# MCUPCB.net
KiCad netlist of a schematic drawn in EasyEDA Pro
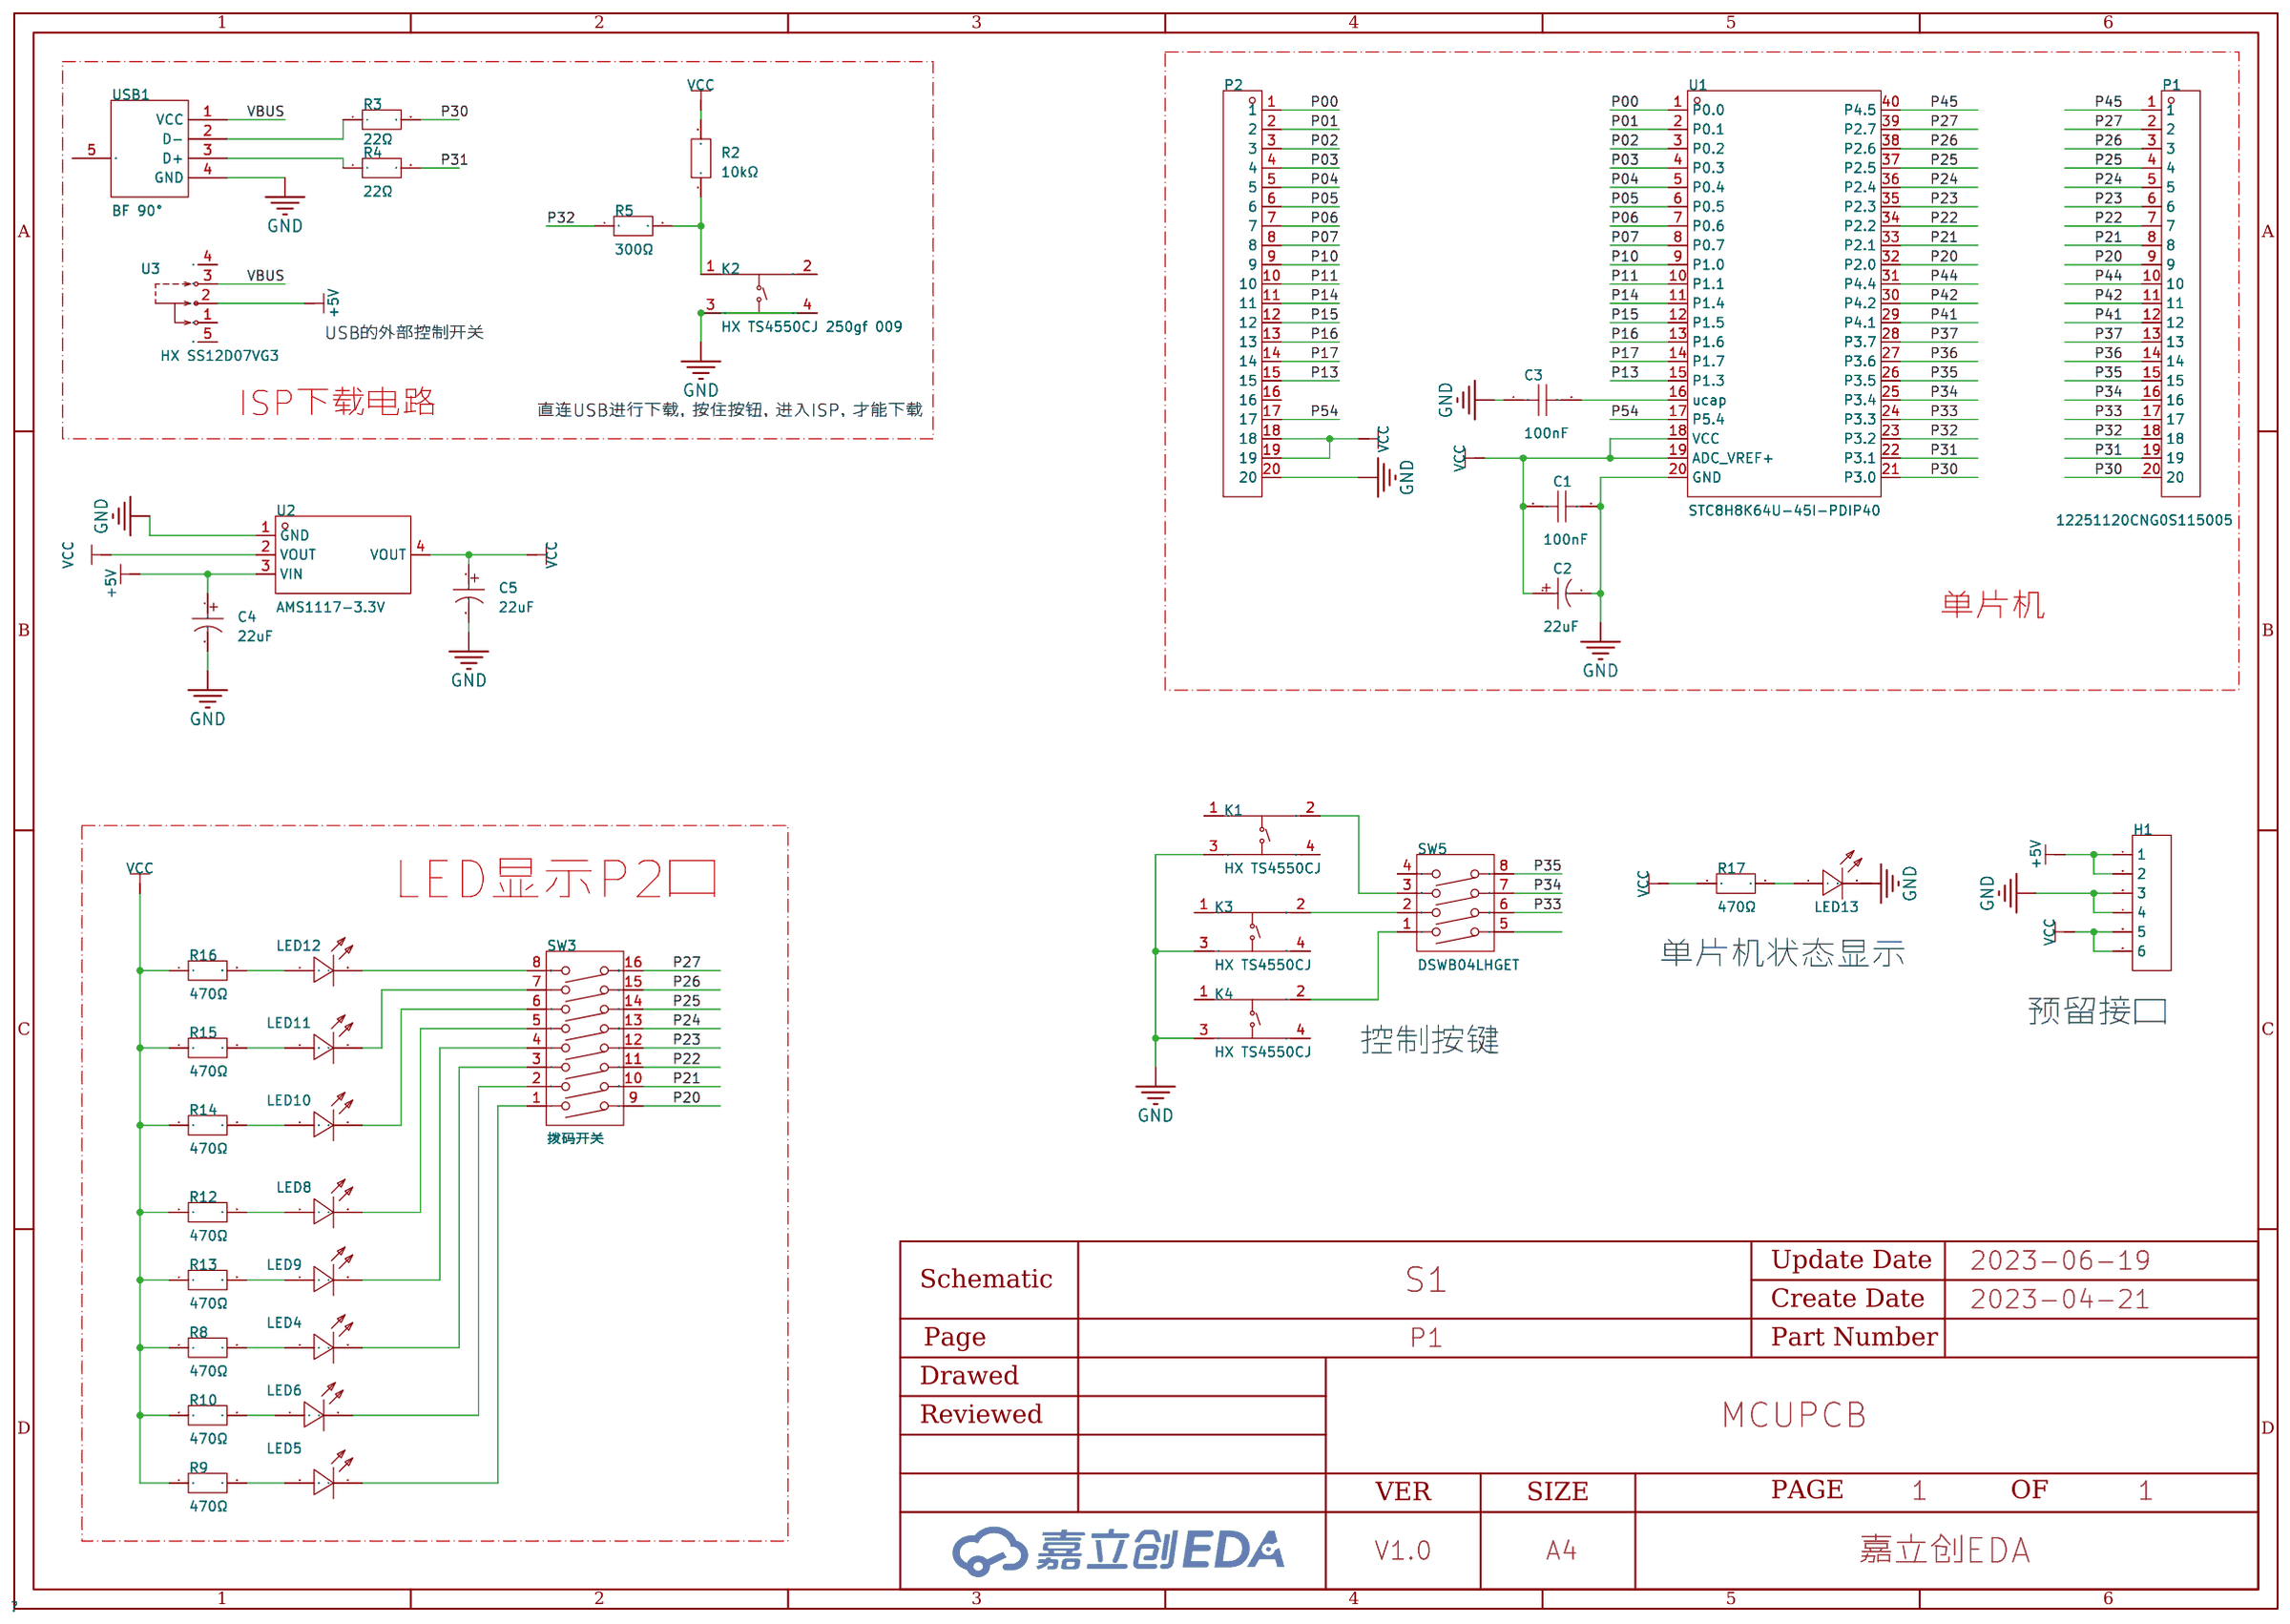
[diagram p0: schematic sheet]

(export (version "E")
  (design (tool "Eeschema 10.0.6"))
  (components
    (comp (ref "C1")
      (value "100nF")
      (footprint "easyedapro:CAP-TH_L4.2-W3.8-P2.54-D0.5")
      (description "容值:100nF;精度:±10%;额定电压:50V;温度系数:X7R;")
      (fields (field (name "Manufacturer Part") "CT4-0805B104K500F1") (field (name "Manufacturer") "FH(风华)"))
      (libsource (lib "easyedapro") (part "CT4-0805B104K500F1"))
    )
    (comp (ref "C2")
      (value "22uF")
      (footprint "easyedapro:CAP-TH_BD4.0-P1.50-D0.8-FD")
      (description "容值:22uF;精度:±20%;额定电压:16V;纹波电流:-;等效串联电阻:-;")
      (fields
        (field (name "Manufacturer Part") "KS226M016C07RR0VH2FP0")
        (field (name "Manufacturer") "CX(承兴)")
      )
      (libsource (lib "easyedapro") (part "22uF 16V 4*7"))
    )
    (comp (ref "C3")
      (value "100nF")
      (footprint "easyedapro:CAP-TH_L4.2-W3.8-P2.54-D0.5")
      (description "容值:100nF;精度:±10%;额定电压:50V;温度系数:X7R;")
      (fields (field (name "Manufacturer Part") "CT4-0805B104K500F1") (field (name "Manufacturer") "FH(风华)"))
      (libsource (lib "easyedapro") (part "CT4-0805B104K500F1"))
    )
    (comp (ref "C4")
      (value "22uF")
      (footprint "easyedapro:CAP-TH_BD4.0-P1.50-D0.8-FD")
      (description "容值:22uF;精度:±20%;额定电压:16V;纹波电流:-;等效串联电阻:-;")
      (fields
        (field (name "Manufacturer Part") "KS226M016C07RR0VH2FP0")
        (field (name "Manufacturer") "CX(承兴)")
      )
      (libsource (lib "easyedapro") (part "22uF 16V 4*7"))
    )
    (comp (ref "C5")
      (value "22uF")
      (footprint "easyedapro:CAP-TH_BD4.0-P1.50-D0.8-FD")
      (description "容值:22uF;精度:±20%;额定电压:16V;纹波电流:-;等效串联电阻:-;")
      (fields
        (field (name "Manufacturer Part") "KS226M016C07RR0VH2FP0")
        (field (name "Manufacturer") "CX(承兴)")
      )
      (libsource (lib "easyedapro") (part "22uF 16V 4*7"))
    )
    (comp (ref "H1")
      (value "~")
      (footprint "easyedapro:HDR-TH_6P-P2.54-V-M-1")
      (libsource (lib "easyedapro") (part "Header-Male-2.54_1x6"))
    )
    (comp (ref "K1")
      (value "HX TS4550CJ")
      (footprint "easyedapro:SW-TH_4P-L4.5-W4.5-P3.00-LS5.0")
      (fields (field (name "Manufacturer") "hanxia(韩下)"))
      (libsource (lib "easyedapro") (part "HX TS4550CJ 250GF 009"))
    )
    (comp (ref "K2")
      (value "HX TS4550CJ 250gf 009")
      (footprint "easyedapro:SW-TH_4P-L4.5-W4.5-P3.00-LS5.0")
      (fields (field (name "Manufacturer") "hanxia(韩下)"))
      (libsource (lib "easyedapro") (part "HX TS4550CJ 250GF 009"))
    )
    (comp (ref "K3")
      (value "HX TS4550CJ")
      (footprint "easyedapro:SW-TH_4P-L4.5-W4.5-P3.00-LS5.0")
      (fields (field (name "Manufacturer") "hanxia(韩下)"))
      (libsource (lib "easyedapro") (part "HX TS4550CJ 250GF 009"))
    )
    (comp (ref "K4")
      (value "HX TS4550CJ")
      (footprint "easyedapro:SW-TH_4P-L4.5-W4.5-P3.00-LS5.0")
      (fields (field (name "Manufacturer") "hanxia(韩下)"))
      (libsource (lib "easyedapro") (part "HX TS4550CJ 250GF 009"))
    )
    (comp (ref "LED4")
      (value "TJ-L3FYTLDRMFCSFLC2R-A5")
      (footprint "easyedapro:LED-TH_BD3.8-P2.54-FD")
      (description "发光颜色:橙红;二极管配置:-;主波长:620nm~630nm;色温:-;功率:72mW;安装方式:-;")
      (fields (field (name "Manufacturer") "TOGIALED(统佳)"))
      (libsource (lib "easyedapro") (part "TJ-L3FYTLDRMFCSFLC2R-A5"))
    )
    (comp (ref "LED5")
      (value "TJ-L3FYTLDRMFCSFLC2R-A5")
      (footprint "easyedapro:LED-TH_BD3.8-P2.54-FD")
      (description "发光颜色:橙红;二极管配置:-;主波长:620nm~630nm;色温:-;功率:72mW;安装方式:-;")
      (fields (field (name "Manufacturer") "TOGIALED(统佳)"))
      (libsource (lib "easyedapro") (part "TJ-L3FYTLDRMFCSFLC2R-A5"))
    )
    (comp (ref "LED6")
      (value "TJ-L3FYTLDRMFCSFLC2R-A5")
      (footprint "easyedapro:LED-TH_BD3.8-P2.54-FD")
      (description "发光颜色:橙红;二极管配置:-;主波长:620nm~630nm;色温:-;功率:72mW;安装方式:-;")
      (fields (field (name "Manufacturer") "TOGIALED(统佳)"))
      (libsource (lib "easyedapro") (part "TJ-L3FYTLDRMFCSFLC2R-A5"))
    )
    (comp (ref "LED8")
      (value "TJ-L3FYTLDRMFCSFLC2R-A5")
      (footprint "easyedapro:LED-TH_BD3.8-P2.54-FD")
      (description "发光颜色:橙红;二极管配置:-;主波长:620nm~630nm;色温:-;功率:72mW;安装方式:-;")
      (fields (field (name "Manufacturer") "TOGIALED(统佳)"))
      (libsource (lib "easyedapro") (part "TJ-L3FYTLDRMFCSFLC2R-A5"))
    )
    (comp (ref "LED9")
      (value "TJ-L3FYTLDRMFCSFLC2R-A5")
      (footprint "easyedapro:LED-TH_BD3.8-P2.54-FD")
      (description "发光颜色:橙红;二极管配置:-;主波长:620nm~630nm;色温:-;功率:72mW;安装方式:-;")
      (fields (field (name "Manufacturer") "TOGIALED(统佳)"))
      (libsource (lib "easyedapro") (part "TJ-L3FYTLDRMFCSFLC2R-A5"))
    )
    (comp (ref "LED10")
      (value "TJ-L3FYTLDRMFCSFLC2R-A5")
      (footprint "easyedapro:LED-TH_BD3.8-P2.54-FD")
      (description "发光颜色:橙红;二极管配置:-;主波长:620nm~630nm;色温:-;功率:72mW;安装方式:-;")
      (fields (field (name "Manufacturer") "TOGIALED(统佳)"))
      (libsource (lib "easyedapro") (part "TJ-L3FYTLDRMFCSFLC2R-A5"))
    )
    (comp (ref "LED11")
      (value "TJ-L3FYTLDRMFCSFLC2R-A5")
      (footprint "easyedapro:LED-TH_BD3.8-P2.54-FD")
      (description "发光颜色:橙红;二极管配置:-;主波长:620nm~630nm;色温:-;功率:72mW;安装方式:-;")
      (fields (field (name "Manufacturer") "TOGIALED(统佳)"))
      (libsource (lib "easyedapro") (part "TJ-L3FYTLDRMFCSFLC2R-A5"))
    )
    (comp (ref "LED12")
      (value "TJ-L3FYTLDRMFCSFLC2R-A5")
      (footprint "easyedapro:LED-TH_BD3.8-P2.54-FD")
      (description "发光颜色:橙红;二极管配置:-;主波长:620nm~630nm;色温:-;功率:72mW;安装方式:-;")
      (fields (field (name "Manufacturer") "TOGIALED(统佳)"))
      (libsource (lib "easyedapro") (part "TJ-L3FYTLDRMFCSFLC2R-A5"))
    )
    (comp (ref "LED13")
      (value "TJ-L3FYTLDRMFCSFLC2R-A5")
      (footprint "easyedapro:LED-TH_BD3.8-P2.54-FD")
      (description "发光颜色:橙红;二极管配置:-;主波长:620nm~630nm;色温:-;功率:72mW;安装方式:-;")
      (fields (field (name "Manufacturer") "TOGIALED(统佳)"))
      (libsource (lib "easyedapro") (part "TJ-L3FYTLDRMFCSFLC2R-A5"))
    )
    (comp (ref "P1")
      (value "12251120CNG0S115005")
      (footprint "easyedapro:HDR-TH_20P-P2.54-V-M-1")
      (fields (field (name "Manufacturer") "JILN(锦凌)"))
      (libsource (lib "easyedapro") (part "12251120CNG0S115005"))
    )
    (comp (ref "P2")
      (value "12251120CNG0S115005")
      (footprint "easyedapro:HDR-TH_20P-P2.54-V-M-1")
      (fields (field (name "Manufacturer") "JILN(锦凌)"))
      (libsource (lib "easyedapro") (part "12251120CNG0S115005"))
    )
    (comp (ref "R2")
      (value "10kΩ")
      (footprint "easyedapro:RES-TH_BD2.7-L6.2-P10.20-D0.4")
      (description "电阻类型:碳膜电阻;阻值:10kΩ;精度:±5%;")
      (fields (field (name "Manufacturer Part") "CR1/4W-10K±5%-ST52") (field (name "Manufacturer") "VO(翔胜)"))
      (libsource (lib "easyedapro") (part "CR1/4W-10K±5%-ST52"))
    )
    (comp (ref "R3")
      (value "22Ω")
      (footprint "easyedapro:RES-TH_BD2.7-L6.2-P10.20-D0.4")
      (description "电阻类型:碳膜电阻;阻值:22Ω;精度:±5%;功率:250mW;温度系数:±350ppm/°C;最大工作电压:250V;工作温度范围:-55°C~+155°C;")
      (fields (field (name "Manufacturer Part") "CR1/4W-22Ω±5%-RT52") (field (name "Manufacturer") "VO(翔胜)"))
      (libsource (lib "easyedapro") (part "CR1/4W-22Ω±5%-RT52"))
    )
    (comp (ref "R4")
      (value "22Ω")
      (footprint "easyedapro:RES-TH_BD2.7-L6.2-P10.20-D0.4")
      (description "电阻类型:碳膜电阻;阻值:22Ω;精度:±5%;功率:250mW;温度系数:±350ppm/°C;最大工作电压:250V;工作温度范围:-55°C~+155°C;")
      (fields (field (name "Manufacturer Part") "CR1/4W-22Ω±5%-RT52") (field (name "Manufacturer") "VO(翔胜)"))
      (libsource (lib "easyedapro") (part "CR1/4W-22Ω±5%-RT52"))
    )
    (comp (ref "R5")
      (value "300Ω")
      (footprint "easyedapro:RES-TH_BD2.7-L6.2-P10.20-D0.4")
      (description "电阻类型:碳膜电阻;阻值:300Ω;精度:±5%;功率:250mW;温度系数:±350ppm/°C;最大工作电压:250V;工作温度范围:-55°C~+155°C;")
      (fields (field (name "Manufacturer Part") "CR1/4W-300Ω±5%-ST26") (field (name "Manufacturer") "VO(翔胜)"))
      (libsource (lib "easyedapro") (part "CR1/4W-300Ω±5%-ST26"))
    )
    (comp (ref "R8")
      (value "470Ω")
      (footprint "easyedapro:RES-TH_BD2.3-L6.5-P10.50-D0.5")
      (description "电阻类型:碳膜电阻;阻值:470Ω;精度:±5%;功率:250mW;温度系数:-1500ppm/°C~+300ppm/°C;最大工作电压:250V;工作温度范围:-55°C~+125°C;")
      (fields (field (name "Manufacturer Part") "CF1/4W-470Ω±5%T52") (field (name "Manufacturer") "华星机电"))
      (libsource (lib "easyedapro") (part "CF1/4W-470Ω±5%T52"))
    )
    (comp (ref "R9")
      (value "470Ω")
      (footprint "easyedapro:RES-TH_BD2.3-L6.5-P10.50-D0.5")
      (description "电阻类型:碳膜电阻;阻值:470Ω;精度:±5%;功率:250mW;温度系数:-1500ppm/°C~+300ppm/°C;最大工作电压:250V;工作温度范围:-55°C~+125°C;")
      (fields (field (name "Manufacturer Part") "CF1/4W-470Ω±5%T52") (field (name "Manufacturer") "华星机电"))
      (libsource (lib "easyedapro") (part "CF1/4W-470Ω±5%T52"))
    )
    (comp (ref "R10")
      (value "470Ω")
      (footprint "easyedapro:RES-TH_BD2.3-L6.5-P10.50-D0.5")
      (description "电阻类型:碳膜电阻;阻值:470Ω;精度:±5%;功率:250mW;温度系数:-1500ppm/°C~+300ppm/°C;最大工作电压:250V;工作温度范围:-55°C~+125°C;")
      (fields (field (name "Manufacturer Part") "CF1/4W-470Ω±5%T52") (field (name "Manufacturer") "华星机电"))
      (libsource (lib "easyedapro") (part "CF1/4W-470Ω±5%T52"))
    )
    (comp (ref "R12")
      (value "470Ω")
      (footprint "easyedapro:RES-TH_BD2.3-L6.5-P10.50-D0.5")
      (description "电阻类型:碳膜电阻;阻值:470Ω;精度:±5%;功率:250mW;温度系数:-1500ppm/°C~+300ppm/°C;最大工作电压:250V;工作温度范围:-55°C~+125°C;")
      (fields (field (name "Manufacturer Part") "CF1/4W-470Ω±5%T52") (field (name "Manufacturer") "华星机电"))
      (libsource (lib "easyedapro") (part "CF1/4W-470Ω±5%T52"))
    )
    (comp (ref "R13")
      (value "470Ω")
      (footprint "easyedapro:RES-TH_BD2.3-L6.5-P10.50-D0.5")
      (description "电阻类型:碳膜电阻;阻值:470Ω;精度:±5%;功率:250mW;温度系数:-1500ppm/°C~+300ppm/°C;最大工作电压:250V;工作温度范围:-55°C~+125°C;")
      (fields (field (name "Manufacturer Part") "CF1/4W-470Ω±5%T52") (field (name "Manufacturer") "华星机电"))
      (libsource (lib "easyedapro") (part "CF1/4W-470Ω±5%T52"))
    )
    (comp (ref "R14")
      (value "470Ω")
      (footprint "easyedapro:RES-TH_BD2.3-L6.5-P10.50-D0.5")
      (description "电阻类型:碳膜电阻;阻值:470Ω;精度:±5%;功率:250mW;温度系数:-1500ppm/°C~+300ppm/°C;最大工作电压:250V;工作温度范围:-55°C~+125°C;")
      (fields (field (name "Manufacturer Part") "CF1/4W-470Ω±5%T52") (field (name "Manufacturer") "华星机电"))
      (libsource (lib "easyedapro") (part "CF1/4W-470Ω±5%T52"))
    )
    (comp (ref "R15")
      (value "470Ω")
      (footprint "easyedapro:RES-TH_BD2.3-L6.5-P10.50-D0.5")
      (description "电阻类型:碳膜电阻;阻值:470Ω;精度:±5%;功率:250mW;温度系数:-1500ppm/°C~+300ppm/°C;最大工作电压:250V;工作温度范围:-55°C~+125°C;")
      (fields (field (name "Manufacturer Part") "CF1/4W-470Ω±5%T52") (field (name "Manufacturer") "华星机电"))
      (libsource (lib "easyedapro") (part "CF1/4W-470Ω±5%T52"))
    )
    (comp (ref "R16")
      (value "470Ω")
      (footprint "easyedapro:RES-TH_BD2.3-L6.5-P10.50-D0.5")
      (description "电阻类型:碳膜电阻;阻值:470Ω;精度:±5%;功率:250mW;温度系数:-1500ppm/°C~+300ppm/°C;最大工作电压:250V;工作温度范围:-55°C~+125°C;")
      (fields (field (name "Manufacturer Part") "CF1/4W-470Ω±5%T52") (field (name "Manufacturer") "华星机电"))
      (libsource (lib "easyedapro") (part "CF1/4W-470Ω±5%T52"))
    )
    (comp (ref "R17")
      (value "470Ω")
      (footprint "easyedapro:RES-TH_BD2.3-L6.5-P10.50-D0.5")
      (description "电阻类型:碳膜电阻;阻值:470Ω;精度:±5%;功率:250mW;温度系数:-1500ppm/°C~+300ppm/°C;最大工作电压:250V;工作温度范围:-55°C~+125°C;")
      (fields (field (name "Manufacturer Part") "CF1/4W-470Ω±5%T52") (field (name "Manufacturer") "华星机电"))
      (libsource (lib "easyedapro") (part "CF1/4W-470Ω±5%T52"))
    )
    (comp (ref "SW3")
      (value "拨码开关")
      (footprint "easyedapro:SW-TH_DSWB08LHGET")
      (description "类型:平拨，凸起式;电路结构:单刀单掷;开关位数:8;引脚间距:2.54mm;颜色:红色;")
      (fields (field (name "Manufacturer") "YE"))
      (libsource (lib "easyedapro") (part "DSWB08LHGET"))
    )
    (comp (ref "SW5")
      (value "DSWB04LHGET")
      (footprint "easyedapro:SW-TH_DSWB04LHGET")
      (description "类型:平拨，凸起式;电路结构:单刀单掷;开关位数:4;引脚间距:2.54mm;颜色:红色;")
      (fields (field (name "Manufacturer") "YE"))
      (libsource (lib "easyedapro") (part "DSWB04LHGET"))
    )
    (comp (ref "U1")
      (value "STC8H8K64U-45I-PDIP40")
      (footprint "easyedapro:PDIP-40_L52.3-W13.7-P2.54-LS15.5-BL")
      (description "单片机@@全速USB，DMA支持：TFT彩屏接口，4个串口，SPI,ADC,RTC")
      (fields (field (name "Manufacturer") "STC(宏晶)"))
      (libsource (lib "easyedapro") (part "STC8H8K64U-45I-PDIP40"))
    )
    (comp (ref "U2")
      (value "AMS1117-3.3V")
      (footprint "easyedapro:SOT-223_L6.5-W3.5-P2.30-LS7.0-BR")
      (description "输出类型:固定;输出极性:正;最大输入电压:12V;输出电压:3.3V;输出电流:800mA;电源纹波抑制比(PSRR):75dB@(10kHz);")
      (fields (field (name "Manufacturer") "FM(富满)"))
      (libsource (lib "easyedapro") (part "SC1117-3.3V"))
    )
    (comp (ref "U3")
      (value "HX SS12D07VG3")
      (footprint "easyedapro:SW-TH_SS12D07VG3")
      (fields (field (name "Manufacturer") "hanxia(韩下)"))
      (libsource (lib "easyedapro") (part "HX SS12D07VG3"))
    )
    (comp (ref "USB1")
      (value "BF 90°")
      (footprint "easyedapro:USB-B_TH_BF90")
      (description "连接器类型:Type-B;标准:USB 2.0;公母:母座;触点数量:4;端口数量:1;安装方式:弯插;额定电流 - 电源:1.5A;工作温度范围:-25°C~+85°C;")
      (fields (field (name "Manufacturer") "SHOU HAN(首韩)"))
      (libsource (lib "easyedapro") (part "BF 90°"))
    )
  )
  (nets
    (net (code "1") (name "+5V") (class "Default")
      (node (ref "C4") (pin "1") (pinfunction "1_1") (pintype "input"))
      (node (ref "H1") (pin "1") (pinfunction "1_1") (pintype "input"))
      (node (ref "H1") (pin "2") (pinfunction "2_2") (pintype "input"))
      (node (ref "U2") (pin "3") (pinfunction "VIN_3") (pintype "input"))
      (node (ref "U3") (pin "2") (pinfunction "2_2") (pintype "input"))
    )
    (net (code "2") (name "/P00") (class "Default")
      (node (ref "P2") (pin "1") (pinfunction "1_1") (pintype "input"))
      (node (ref "U1") (pin "1") (pinfunction "P0.0_1") (pintype "input"))
    )
    (net (code "3") (name "/P01") (class "Default")
      (node (ref "P2") (pin "2") (pinfunction "2_2") (pintype "input"))
      (node (ref "U1") (pin "2") (pinfunction "P0.1_2") (pintype "input"))
    )
    (net (code "4") (name "/P02") (class "Default")
      (node (ref "P2") (pin "3") (pinfunction "3_3") (pintype "input"))
      (node (ref "U1") (pin "3") (pinfunction "P0.2_3") (pintype "input"))
    )
    (net (code "5") (name "/P03") (class "Default")
      (node (ref "P2") (pin "4") (pinfunction "4_4") (pintype "input"))
      (node (ref "U1") (pin "4") (pinfunction "P0.3_4") (pintype "input"))
    )
    (net (code "6") (name "/P04") (class "Default")
      (node (ref "P2") (pin "5") (pinfunction "5_5") (pintype "input"))
      (node (ref "U1") (pin "5") (pinfunction "P0.4_5") (pintype "input"))
    )
    (net (code "7") (name "/P05") (class "Default")
      (node (ref "P2") (pin "6") (pinfunction "6_6") (pintype "input"))
      (node (ref "U1") (pin "6") (pinfunction "P0.5_6") (pintype "input"))
    )
    (net (code "8") (name "/P06") (class "Default")
      (node (ref "P2") (pin "7") (pinfunction "7_7") (pintype "input"))
      (node (ref "U1") (pin "7") (pinfunction "P0.6_7") (pintype "input"))
    )
    (net (code "9") (name "/P07") (class "Default")
      (node (ref "P2") (pin "8") (pinfunction "8_8") (pintype "input"))
      (node (ref "U1") (pin "8") (pinfunction "P0.7_8") (pintype "input"))
    )
    (net (code "10") (name "/P10") (class "Default")
      (node (ref "P2") (pin "9") (pinfunction "9_9") (pintype "input"))
      (node (ref "U1") (pin "9") (pinfunction "P1.0_9") (pintype "input"))
    )
    (net (code "11") (name "/P11") (class "Default")
      (node (ref "P2") (pin "10") (pinfunction "10_10") (pintype "input"))
      (node (ref "U1") (pin "10") (pinfunction "P1.1_10") (pintype "input"))
    )
    (net (code "12") (name "/P13") (class "Default")
      (node (ref "P2") (pin "15") (pinfunction "15_15") (pintype "input"))
      (node (ref "U1") (pin "15") (pinfunction "P1.3_15") (pintype "input"))
    )
    (net (code "13") (name "/P14") (class "Default")
      (node (ref "P2") (pin "11") (pinfunction "11_11") (pintype "input"))
      (node (ref "U1") (pin "11") (pinfunction "P1.4_11") (pintype "input"))
    )
    (net (code "14") (name "/P15") (class "Default")
      (node (ref "P2") (pin "12") (pinfunction "12_12") (pintype "input"))
      (node (ref "U1") (pin "12") (pinfunction "P1.5_12") (pintype "input"))
    )
    (net (code "15") (name "/P16") (class "Default")
      (node (ref "P2") (pin "13") (pinfunction "13_13") (pintype "input"))
      (node (ref "U1") (pin "13") (pinfunction "P1.6_13") (pintype "input"))
    )
    (net (code "16") (name "/P17") (class "Default")
      (node (ref "P2") (pin "14") (pinfunction "14_14") (pintype "input"))
      (node (ref "U1") (pin "14") (pinfunction "P1.7_14") (pintype "input"))
    )
    (net (code "17") (name "/P20") (class "Default")
      (node (ref "P1") (pin "9") (pinfunction "9_9") (pintype "input"))
      (node (ref "SW3") (pin "9") (pinfunction "9_9") (pintype "input"))
      (node (ref "U1") (pin "32") (pinfunction "P2.0_32") (pintype "input"))
    )
    (net (code "18") (name "/P21") (class "Default")
      (node (ref "P1") (pin "8") (pinfunction "8_8") (pintype "input"))
      (node (ref "SW3") (pin "10") (pinfunction "10_10") (pintype "input"))
      (node (ref "U1") (pin "33") (pinfunction "P2.1_33") (pintype "input"))
    )
    (net (code "19") (name "/P22") (class "Default")
      (node (ref "P1") (pin "7") (pinfunction "7_7") (pintype "input"))
      (node (ref "SW3") (pin "11") (pinfunction "11_11") (pintype "input"))
      (node (ref "U1") (pin "34") (pinfunction "P2.2_34") (pintype "input"))
    )
    (net (code "20") (name "/P23") (class "Default")
      (node (ref "P1") (pin "6") (pinfunction "6_6") (pintype "input"))
      (node (ref "SW3") (pin "12") (pinfunction "12_12") (pintype "input"))
      (node (ref "U1") (pin "35") (pinfunction "P2.3_35") (pintype "input"))
    )
    (net (code "21") (name "/P24") (class "Default")
      (node (ref "P1") (pin "5") (pinfunction "5_5") (pintype "input"))
      (node (ref "SW3") (pin "13") (pinfunction "13_13") (pintype "input"))
      (node (ref "U1") (pin "36") (pinfunction "P2.4_36") (pintype "input"))
    )
    (net (code "22") (name "/P25") (class "Default")
      (node (ref "P1") (pin "4") (pinfunction "4_4") (pintype "input"))
      (node (ref "SW3") (pin "14") (pinfunction "14_14") (pintype "input"))
      (node (ref "U1") (pin "37") (pinfunction "P2.5_37") (pintype "input"))
    )
    (net (code "23") (name "/P26") (class "Default")
      (node (ref "P1") (pin "3") (pinfunction "3_3") (pintype "input"))
      (node (ref "SW3") (pin "15") (pinfunction "15_15") (pintype "input"))
      (node (ref "U1") (pin "38") (pinfunction "P2.6_38") (pintype "input"))
    )
    (net (code "24") (name "/P27") (class "Default")
      (node (ref "P1") (pin "2") (pinfunction "2_2") (pintype "input"))
      (node (ref "SW3") (pin "16") (pinfunction "16_16") (pintype "input"))
      (node (ref "U1") (pin "39") (pinfunction "P2.7_39") (pintype "input"))
    )
    (net (code "25") (name "/P30") (class "Default")
      (node (ref "P1") (pin "20") (pinfunction "20_20") (pintype "input"))
      (node (ref "R3") (pin "2") (pinfunction "2_2") (pintype "input"))
      (node (ref "U1") (pin "21") (pinfunction "P3.0_21") (pintype "input"))
    )
    (net (code "26") (name "/P31") (class "Default")
      (node (ref "P1") (pin "19") (pinfunction "19_19") (pintype "input"))
      (node (ref "R4") (pin "2") (pinfunction "2_2") (pintype "input"))
      (node (ref "U1") (pin "22") (pinfunction "P3.1_22") (pintype "input"))
    )
    (net (code "27") (name "/P32") (class "Default")
      (node (ref "P1") (pin "18") (pinfunction "18_18") (pintype "input"))
      (node (ref "R5") (pin "1") (pinfunction "1_1") (pintype "input"))
      (node (ref "U1") (pin "23") (pinfunction "P3.2_23") (pintype "input"))
    )
    (net (code "28") (name "/P33") (class "Default")
      (node (ref "P1") (pin "17") (pinfunction "17_17") (pintype "input"))
      (node (ref "SW5") (pin "6") (pinfunction "6_6") (pintype "input"))
      (node (ref "U1") (pin "24") (pinfunction "P3.3_24") (pintype "input"))
    )
    (net (code "29") (name "/P34") (class "Default")
      (node (ref "P1") (pin "16") (pinfunction "16_16") (pintype "input"))
      (node (ref "SW5") (pin "7") (pinfunction "7_7") (pintype "input"))
      (node (ref "U1") (pin "25") (pinfunction "P3.4_25") (pintype "input"))
    )
    (net (code "30") (name "/P35") (class "Default")
      (node (ref "P1") (pin "15") (pinfunction "15_15") (pintype "input"))
      (node (ref "SW5") (pin "8") (pinfunction "8_8") (pintype "input"))
      (node (ref "U1") (pin "26") (pinfunction "P3.5_26") (pintype "input"))
    )
    (net (code "31") (name "/P36") (class "Default")
      (node (ref "P1") (pin "14") (pinfunction "14_14") (pintype "input"))
      (node (ref "U1") (pin "27") (pinfunction "P3.6_27") (pintype "input"))
    )
    (net (code "32") (name "/P37") (class "Default")
      (node (ref "P1") (pin "13") (pinfunction "13_13") (pintype "input"))
      (node (ref "U1") (pin "28") (pinfunction "P3.7_28") (pintype "input"))
    )
    (net (code "33") (name "/P41") (class "Default")
      (node (ref "P1") (pin "12") (pinfunction "12_12") (pintype "input"))
      (node (ref "U1") (pin "29") (pinfunction "P4.1_29") (pintype "input"))
    )
    (net (code "34") (name "/P42") (class "Default")
      (node (ref "P1") (pin "11") (pinfunction "11_11") (pintype "input"))
      (node (ref "U1") (pin "30") (pinfunction "P4.2_30") (pintype "input"))
    )
    (net (code "35") (name "/P44") (class "Default")
      (node (ref "P1") (pin "10") (pinfunction "10_10") (pintype "input"))
      (node (ref "U1") (pin "31") (pinfunction "P4.4_31") (pintype "input"))
    )
    (net (code "36") (name "/P45") (class "Default")
      (node (ref "P1") (pin "1") (pinfunction "1_1") (pintype "input"))
      (node (ref "U1") (pin "40") (pinfunction "P4.5_40") (pintype "input"))
    )
    (net (code "37") (name "/P54") (class "Default")
      (node (ref "P2") (pin "17") (pinfunction "17_17") (pintype "input"))
      (node (ref "U1") (pin "17") (pinfunction "P5.4_17") (pintype "input"))
    )
    (net (code "38") (name "/VBUS") (class "Default")
      (node (ref "U3") (pin "3") (pinfunction "3_3") (pintype "input"))
      (node (ref "USB1") (pin "1") (pinfunction "VCC_1") (pintype "input"))
    )
    (net (code "39") (name "GND") (class "Default")
      (node (ref "C1") (pin "1") (pinfunction "1_1") (pintype "input"))
      (node (ref "C2") (pin "2") (pinfunction "2_2") (pintype "input"))
      (node (ref "C3") (pin "1") (pinfunction "1_1") (pintype "input"))
      (node (ref "C4") (pin "2") (pinfunction "2_2") (pintype "input"))
      (node (ref "C5") (pin "2") (pinfunction "2_2") (pintype "input"))
      (node (ref "H1") (pin "3") (pinfunction "3_3") (pintype "input"))
      (node (ref "H1") (pin "4") (pinfunction "4_4") (pintype "input"))
      (node (ref "K1") (pin "3") (pinfunction "C_3") (pintype "input"))
      (node (ref "K2") (pin "3") (pinfunction "C_3") (pintype "input"))
      (node (ref "K2") (pin "4") (pinfunction "D_4") (pintype "input"))
      (node (ref "K3") (pin "3") (pinfunction "C_3") (pintype "input"))
      (node (ref "K4") (pin "3") (pinfunction "C_3") (pintype "input"))
      (node (ref "LED13") (pin "2") (pinfunction "K_2") (pintype "input"))
      (node (ref "P2") (pin "20") (pinfunction "20_20") (pintype "input"))
      (node (ref "U1") (pin "20") (pinfunction "GND_20") (pintype "input"))
      (node (ref "U2") (pin "1") (pinfunction "GND_1") (pintype "input"))
      (node (ref "USB1") (pin "4") (pinfunction "GND_4") (pintype "input"))
    )
    (net (code "40") (name "Net-(K1-B)") (class "Default")
      (node (ref "K1") (pin "2") (pinfunction "B_2") (pintype "input"))
      (node (ref "SW5") (pin "3") (pinfunction "3_3") (pintype "input"))
    )
    (net (code "41") (name "Net-(K2-A)") (class "Default")
      (node (ref "K2") (pin "1") (pinfunction "A_1") (pintype "input"))
      (node (ref "R2") (pin "1") (pinfunction "1_1") (pintype "input"))
      (node (ref "R5") (pin "2") (pinfunction "2_2") (pintype "input"))
    )
    (net (code "42") (name "Net-(K3-B)") (class "Default")
      (node (ref "K3") (pin "2") (pinfunction "B_2") (pintype "input"))
      (node (ref "SW5") (pin "2") (pinfunction "2_2") (pintype "input"))
    )
    (net (code "43") (name "Net-(K4-B)") (class "Default")
      (node (ref "K4") (pin "2") (pinfunction "B_2") (pintype "input"))
      (node (ref "SW5") (pin "1") (pinfunction "1_1") (pintype "input"))
    )
    (net (code "44") (name "Net-(LED4-A)") (class "Default")
      (node (ref "LED4") (pin "1") (pinfunction "A_1") (pintype "input"))
      (node (ref "R8") (pin "2") (pinfunction "2_2") (pintype "input"))
    )
    (net (code "45") (name "Net-(LED4-K)") (class "Default")
      (node (ref "LED4") (pin "2") (pinfunction "K_2") (pintype "input"))
      (node (ref "SW3") (pin "3") (pinfunction "3_3") (pintype "input"))
    )
    (net (code "46") (name "Net-(LED5-A)") (class "Default")
      (node (ref "LED5") (pin "1") (pinfunction "A_1") (pintype "input"))
      (node (ref "R9") (pin "2") (pinfunction "2_2") (pintype "input"))
    )
    (net (code "47") (name "Net-(LED5-K)") (class "Default")
      (node (ref "LED5") (pin "2") (pinfunction "K_2") (pintype "input"))
      (node (ref "SW3") (pin "1") (pinfunction "1_1") (pintype "input"))
    )
    (net (code "48") (name "Net-(LED6-A)") (class "Default")
      (node (ref "LED6") (pin "1") (pinfunction "A_1") (pintype "input"))
      (node (ref "R10") (pin "2") (pinfunction "2_2") (pintype "input"))
    )
    (net (code "49") (name "Net-(LED6-K)") (class "Default")
      (node (ref "LED6") (pin "2") (pinfunction "K_2") (pintype "input"))
      (node (ref "SW3") (pin "2") (pinfunction "2_2") (pintype "input"))
    )
    (net (code "50") (name "Net-(LED8-A)") (class "Default")
      (node (ref "LED8") (pin "1") (pinfunction "A_1") (pintype "input"))
      (node (ref "R12") (pin "2") (pinfunction "2_2") (pintype "input"))
    )
    (net (code "51") (name "Net-(LED8-K)") (class "Default")
      (node (ref "LED8") (pin "2") (pinfunction "K_2") (pintype "input"))
      (node (ref "SW3") (pin "5") (pinfunction "5_5") (pintype "input"))
    )
    (net (code "52") (name "Net-(LED9-A)") (class "Default")
      (node (ref "LED9") (pin "1") (pinfunction "A_1") (pintype "input"))
      (node (ref "R13") (pin "2") (pinfunction "2_2") (pintype "input"))
    )
    (net (code "53") (name "Net-(LED9-K)") (class "Default")
      (node (ref "LED9") (pin "2") (pinfunction "K_2") (pintype "input"))
      (node (ref "SW3") (pin "4") (pinfunction "4_4") (pintype "input"))
    )
    (net (code "54") (name "Net-(LED10-A)") (class "Default")
      (node (ref "LED10") (pin "1") (pinfunction "A_1") (pintype "input"))
      (node (ref "R14") (pin "2") (pinfunction "2_2") (pintype "input"))
    )
    (net (code "55") (name "Net-(LED10-K)") (class "Default")
      (node (ref "LED10") (pin "2") (pinfunction "K_2") (pintype "input"))
      (node (ref "SW3") (pin "6") (pinfunction "6_6") (pintype "input"))
    )
    (net (code "56") (name "Net-(LED11-A)") (class "Default")
      (node (ref "LED11") (pin "1") (pinfunction "A_1") (pintype "input"))
      (node (ref "R15") (pin "2") (pinfunction "2_2") (pintype "input"))
    )
    (net (code "57") (name "Net-(LED11-K)") (class "Default")
      (node (ref "LED11") (pin "2") (pinfunction "K_2") (pintype "input"))
      (node (ref "SW3") (pin "7") (pinfunction "7_7") (pintype "input"))
    )
    (net (code "58") (name "Net-(LED12-A)") (class "Default")
      (node (ref "LED12") (pin "1") (pinfunction "A_1") (pintype "input"))
      (node (ref "R16") (pin "2") (pinfunction "2_2") (pintype "input"))
    )
    (net (code "59") (name "Net-(LED12-K)") (class "Default")
      (node (ref "LED12") (pin "2") (pinfunction "K_2") (pintype "input"))
      (node (ref "SW3") (pin "8") (pinfunction "8_8") (pintype "input"))
    )
    (net (code "60") (name "Net-(LED13-A)") (class "Default")
      (node (ref "LED13") (pin "1") (pinfunction "A_1") (pintype "input"))
      (node (ref "R17") (pin "2") (pinfunction "2_2") (pintype "input"))
    )
    (net (code "61") (name "Net-(U1-ucap)") (class "Default")
      (node (ref "C3") (pin "2") (pinfunction "2_2") (pintype "input"))
      (node (ref "U1") (pin "16") (pinfunction "ucap_16") (pintype "input"))
    )
    (net (code "62") (name "Net-(USB1-D+)") (class "Default")
      (node (ref "R4") (pin "1") (pinfunction "1_1") (pintype "input"))
      (node (ref "USB1") (pin "3") (pinfunction "D+_3") (pintype "input"))
    )
    (net (code "63") (name "Net-(USB1-D-)") (class "Default")
      (node (ref "R3") (pin "1") (pinfunction "1_1") (pintype "input"))
      (node (ref "USB1") (pin "2") (pinfunction "D-_2") (pintype "input"))
    )
    (net (code "64") (name "VCC") (class "Default")
      (node (ref "C1") (pin "2") (pinfunction "2_2") (pintype "input"))
      (node (ref "C2") (pin "1") (pinfunction "1_1") (pintype "input"))
      (node (ref "C5") (pin "1") (pinfunction "1_1") (pintype "input"))
      (node (ref "H1") (pin "5") (pinfunction "5_5") (pintype "input"))
      (node (ref "H1") (pin "6") (pinfunction "6_6") (pintype "input"))
      (node (ref "P2") (pin "18") (pinfunction "18_18") (pintype "input"))
      (node (ref "P2") (pin "19") (pinfunction "19_19") (pintype "input"))
      (node (ref "R10") (pin "1") (pinfunction "1_1") (pintype "input"))
      (node (ref "R12") (pin "1") (pinfunction "1_1") (pintype "input"))
      (node (ref "R13") (pin "1") (pinfunction "1_1") (pintype "input"))
      (node (ref "R14") (pin "1") (pinfunction "1_1") (pintype "input"))
      (node (ref "R15") (pin "1") (pinfunction "1_1") (pintype "input"))
      (node (ref "R16") (pin "1") (pinfunction "1_1") (pintype "input"))
      (node (ref "R17") (pin "1") (pinfunction "1_1") (pintype "input"))
      (node (ref "R2") (pin "2") (pinfunction "2_2") (pintype "input"))
      (node (ref "R8") (pin "1") (pinfunction "1_1") (pintype "input"))
      (node (ref "R9") (pin "1") (pinfunction "1_1") (pintype "input"))
      (node (ref "U1") (pin "18") (pinfunction "VCC_18") (pintype "input"))
      (node (ref "U1") (pin "19") (pinfunction "ADC_VREF+_19") (pintype "input"))
      (node (ref "U2") (pin "2") (pinfunction "VOUT_2") (pintype "input"))
      (node (ref "U2") (pin "4") (pinfunction "VOUT_4") (pintype "input"))
    )
    (net (code "65") (name "unconnected-(K1-A-Pad1)") (class "Default")
      (node (ref "K1") (pin "1") (pinfunction "A_1") (pintype "input"))
    )
    (net (code "66") (name "unconnected-(K1-D-Pad4)") (class "Default")
      (node (ref "K1") (pin "4") (pinfunction "D_4") (pintype "input"))
    )
    (net (code "67") (name "unconnected-(K2-B-Pad2)") (class "Default")
      (node (ref "K2") (pin "2") (pinfunction "B_2") (pintype "input"))
    )
    (net (code "68") (name "unconnected-(K3-A-Pad1)") (class "Default")
      (node (ref "K3") (pin "1") (pinfunction "A_1") (pintype "input"))
    )
    (net (code "69") (name "unconnected-(K3-D-Pad4)") (class "Default")
      (node (ref "K3") (pin "4") (pinfunction "D_4") (pintype "input"))
    )
    (net (code "70") (name "unconnected-(K4-A-Pad1)") (class "Default")
      (node (ref "K4") (pin "1") (pinfunction "A_1") (pintype "input"))
    )
    (net (code "71") (name "unconnected-(K4-D-Pad4)") (class "Default")
      (node (ref "K4") (pin "4") (pinfunction "D_4") (pintype "input"))
    )
    (net (code "72") (name "unconnected-(P2-Pad16)") (class "Default")
      (node (ref "P2") (pin "16") (pinfunction "16_16") (pintype "input"))
    )
    (net (code "73") (name "unconnected-(SW5-Pad4)") (class "Default")
      (node (ref "SW5") (pin "4") (pinfunction "4_4") (pintype "input"))
    )
    (net (code "74") (name "unconnected-(SW5-Pad5)") (class "Default")
      (node (ref "SW5") (pin "5") (pinfunction "5_5") (pintype "input"))
    )
    (net (code "75") (name "unconnected-(U3-Pad1)") (class "Default")
      (node (ref "U3") (pin "1") (pinfunction "1_1") (pintype "input"))
    )
    (net (code "76") (name "unconnected-(U3-Pad4)") (class "Default")
      (node (ref "U3") (pin "4") (pinfunction "4_4") (pintype "input"))
    )
    (net (code "77") (name "unconnected-(U3-Pad5)") (class "Default")
      (node (ref "U3") (pin "5") (pinfunction "5_5") (pintype "input"))
    )
    (net (code "78") (name "unconnected-(USB1-EH-Pad5)") (class "Default")
      (node (ref "USB1") (pin "5") (pinfunction "EH_5") (pintype "input"))
    )
  )
)
